# spectrum_1kHz_500Hz.net
KiCad netlist of a schematic drawn in Altium Designer
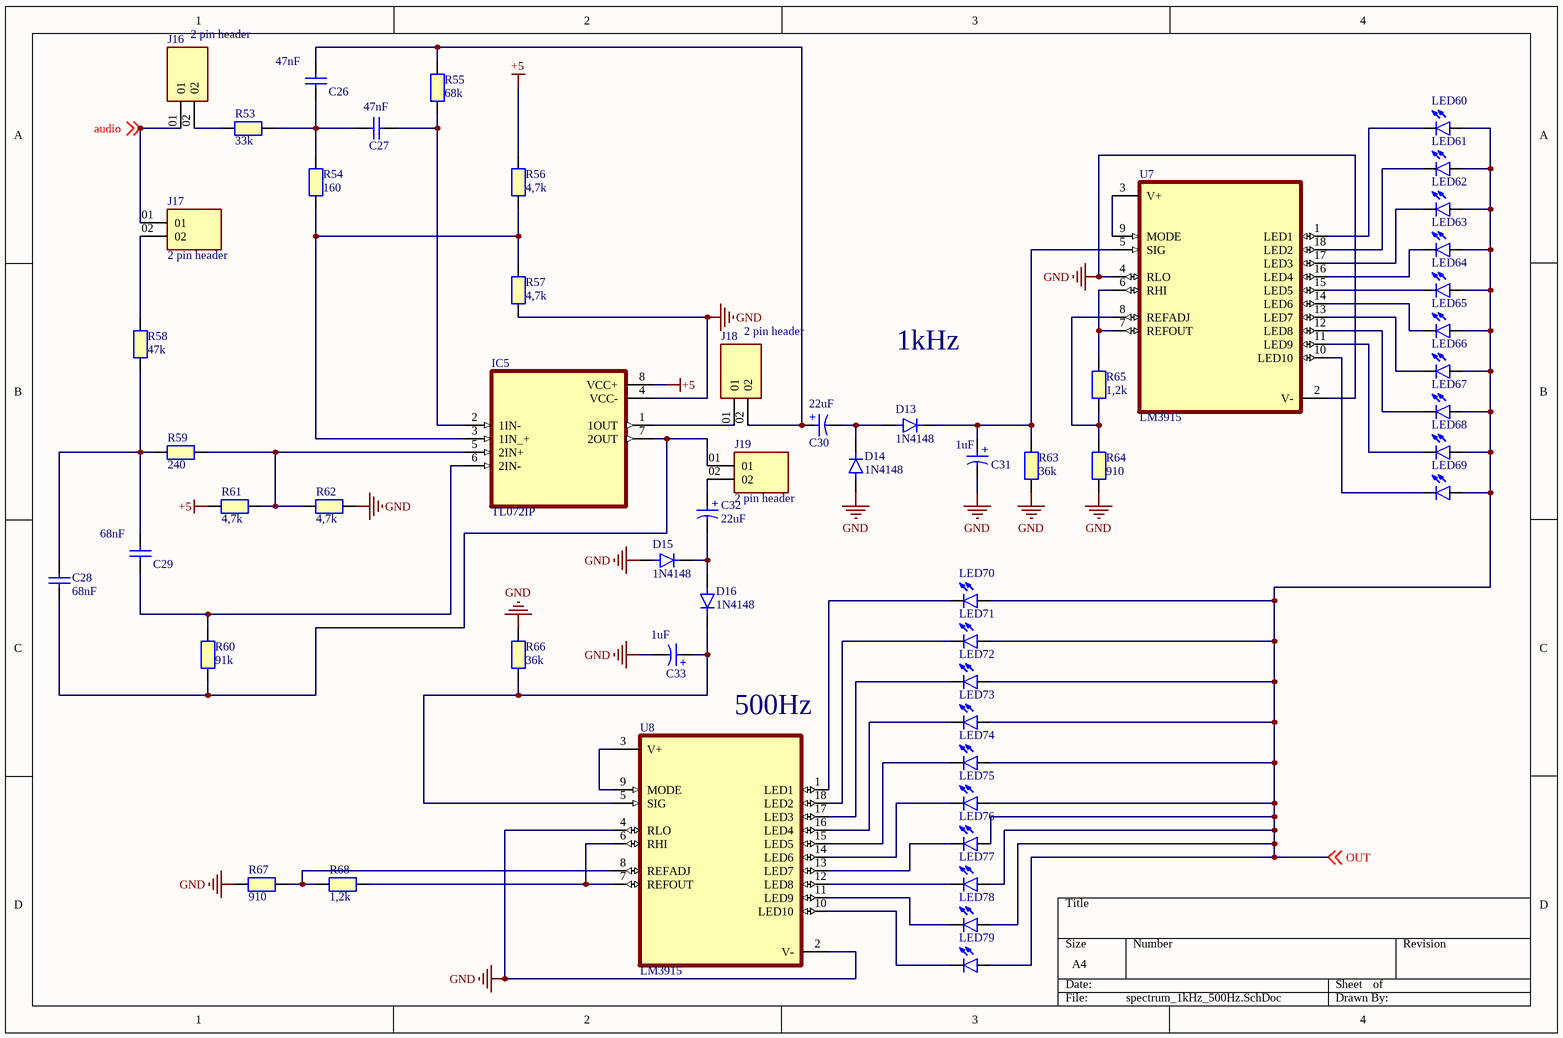
[diagram p0: spectrum_1kHz_500Hz.SchDoc]

(export (version "E")
  (design (tool "Eeschema 10.0.6"))
  (components
    (comp (ref "C26")
      (value "47nF")
      (footprint "CAPC2012X65N")
      (description "47nF ceramic")
      (fields
        (field (name "MANUFACTURER PART NUMBER") "885012004008")
        (field (name "MANUFACTURER") "Wurth Elektronik")
      )
      (libsource (lib "SpectrumComponents") (part "885012004008"))
    )
    (comp (ref "C27")
      (value "47nF")
      (footprint "CAPC2012X65N")
      (description "47nF ceramic")
      (fields
        (field (name "MANUFACTURER PART NUMBER") "885012004008")
        (field (name "MANUFACTURER") "Wurth Elektronik")
      )
      (libsource (lib "SpectrumComponents") (part "885012004008"))
    )
    (comp (ref "C28")
      (value "68nF")
      (footprint "CAPC2012X65N")
      (description "68nF ceramic")
      (fields
        (field (name "MANUFACTURER PART NUMBER") "885012004008")
        (field (name "MANUFACTURER") "Wurth Elektronik")
      )
      (libsource (lib "SpectrumComponents") (part "885012004008"))
    )
    (comp (ref "C29")
      (value "68nF")
      (footprint "CAPC2012X65N")
      (description "68nF ceramic")
      (fields
        (field (name "MANUFACTURER PART NUMBER") "885012004008")
        (field (name "MANUFACTURER") "Wurth Elektronik")
      )
      (libsource (lib "SpectrumComponents") (part "885012004008"))
    )
    (comp (ref "C30")
      (value "22uF")
      (footprint "WCAP-ATG8_D5H11")
      (description "Elco 22uF")
      (fields
        (field (name "MANUFACTURER PART NUMBER") "860010272005")
        (field (name "MANUFACTURER") "Wurth Elektronik")
      )
      (libsource (lib "SpectrumComponents") (part "860010272005"))
    )
    (comp (ref "C31")
      (value "1uF")
      (footprint "WCAP-ATG8_D5H11")
      (description "WCAP-ATG8 Aluminum Electrolytic Capacitor, Radial, THT, D5 x H11mm, 1uF, 10V")
      (fields
        (field (name "MANUFACTURER PART NUMBER") "860010272005")
        (field (name "MANUFACTURER") "Wurth Elektronik")
      )
      (libsource (lib "SpectrumComponents") (part "860010272005"))
    )
    (comp (ref "C32")
      (value "22uF")
      (footprint "WCAP-ATG8_D5H11")
      (description "Elco 22uF")
      (fields
        (field (name "MANUFACTURER PART NUMBER") "860010272005")
        (field (name "MANUFACTURER") "Wurth Elektronik")
      )
      (libsource (lib "SpectrumComponents") (part "860010272005"))
    )
    (comp (ref "C33")
      (value "1uF")
      (footprint "WCAP-ATG8_D5H11")
      (description "WCAP-ATG8 Aluminum Electrolytic Capacitor, Radial, THT, D5 x H11mm, 1µF, 10V")
      (fields
        (field (name "MANUFACTURER PART NUMBER") "860010272005")
        (field (name "MANUFACTURER") "Wurth Elektronik")
      )
      (libsource (lib "SpectrumComponents") (part "860010272005"))
    )
    (comp (ref "D13")
      (value "1N4148")
      (footprint "DIOAD829W49L456D191")
      (description "Diode Standard 75V 200mA Surface Mount SOD-523F")
      (fields (field (name "MF") "ON Semiconductor"))
      (libsource (lib "SpectrumComponents") (part "1N4148"))
    )
    (comp (ref "D14")
      (value "1N4148")
      (footprint "DIOAD829W49L456D191")
      (description "Diode Standard 75V 200mA Surface Mount SOD-523F")
      (fields (field (name "MF") "ON Semiconductor"))
      (libsource (lib "SpectrumComponents") (part "1N4148"))
    )
    (comp (ref "D15")
      (value "1N4148")
      (footprint "DIOAD829W49L456D191")
      (description "Diode Standard 75V 200mA Surface Mount SOD-523F")
      (fields (field (name "MF") "ON Semiconductor"))
      (libsource (lib "SpectrumComponents") (part "1N4148"))
    )
    (comp (ref "D16")
      (value "1N4148")
      (footprint "DIOAD829W49L456D191")
      (description "Diode Standard 75V 200mA Surface Mount SOD-523F")
      (fields (field (name "MF") "ON Semiconductor"))
      (libsource (lib "SpectrumComponents") (part "1N4148"))
    )
    (comp (ref "IC5")
      (value "TL072IP")
      (footprint "DIP794W45P254L959H508Q8")
      (description "Dual, 30-V, 3-MHz, high slew rate (13-V/Âµs), In to V+, JFET-input op amp")
      (fields (field (name "MF") "Texas Instruments"))
      (libsource (lib "SpectrumComponents") (part "TL072IP"))
    )
    (comp (ref "J16")
      (value "2 pin header")
      (footprint "SpectrumComponents:SAMTEC_HTSW-102-07-TM-S")
      (description "2 pin header Jumper")
      (fields (field (name "MP") "HTSW10207TMS") (field (name "MF") "Samtec"))
      (libsource (lib "SpectrumComponents") (part "2 pin header"))
    )
    (comp (ref "J17")
      (value "2 pin header")
      (footprint "SpectrumComponents:SAMTEC_HTSW-102-07-TM-S")
      (description "2 pin header Jumper")
      (fields (field (name "MP") "HTSW10207TMS") (field (name "MF") "Samtec"))
      (libsource (lib "") (part "2 pin header_1"))
    )
    (comp (ref "J18")
      (value "2 pin header")
      (footprint "SpectrumComponents:SAMTEC_HTSW-102-07-TM-S")
      (description "2 pin header Jumper")
      (fields (field (name "MP") "HTSW10207TMS") (field (name "MF") "Samtec"))
      (libsource (lib "SpectrumComponents") (part "2 pin header"))
    )
    (comp (ref "J19")
      (value "2 pin header")
      (footprint "SpectrumComponents:SAMTEC_HTSW-102-07-TM-S")
      (description "2 pin header Jumper")
      (fields (field (name "MP") "HTSW10207TMS") (field (name "MF") "Samtec"))
      (libsource (lib "") (part "2 pin header_1"))
    )
    (comp (ref "LED60")
      (value "LED 2x3x4")
      (footprint "LED 2x3x4mm")
      (description "Green 569nm LED Indication - Discrete 1.9V Radial")
      (fields (field (name "MP") "TLLG4400") (field (name "MF") "Vishay Semiconductors"))
      (libsource (lib "SpectrumComponents") (part "LED 2x3x4"))
    )
    (comp (ref "LED61")
      (value "LED 2x3x4")
      (footprint "LED 2x3x4mm")
      (description "Green 569nm LED Indication - Discrete 1.9V Radial")
      (fields (field (name "MP") "TLLG4400") (field (name "MF") "Vishay Semiconductors"))
      (libsource (lib "SpectrumComponents") (part "LED 2x3x4"))
    )
    (comp (ref "LED62")
      (value "LED 2x3x4")
      (footprint "LED 2x3x4mm")
      (description "Green 569nm LED Indication - Discrete 1.9V Radial")
      (fields (field (name "MP") "TLLG4400") (field (name "MF") "Vishay Semiconductors"))
      (libsource (lib "SpectrumComponents") (part "LED 2x3x4"))
    )
    (comp (ref "LED63")
      (value "LED 2x3x4")
      (footprint "LED 2x3x4mm")
      (description "Green 569nm LED Indication - Discrete 1.9V Radial")
      (fields (field (name "MP") "TLLG4400") (field (name "MF") "Vishay Semiconductors"))
      (libsource (lib "SpectrumComponents") (part "LED 2x3x4"))
    )
    (comp (ref "LED64")
      (value "LED 2x3x4")
      (footprint "LED 2x3x4mm")
      (description "Green 569nm LED Indication - Discrete 1.9V Radial")
      (fields (field (name "MP") "TLLG4400") (field (name "MF") "Vishay Semiconductors"))
      (libsource (lib "SpectrumComponents") (part "LED 2x3x4"))
    )
    (comp (ref "LED65")
      (value "LED 2x3x4")
      (footprint "LED 2x3x4mm")
      (description "Green 569nm LED Indication - Discrete 1.9V Radial")
      (fields (field (name "MP") "TLLG4400") (field (name "MF") "Vishay Semiconductors"))
      (libsource (lib "SpectrumComponents") (part "LED 2x3x4"))
    )
    (comp (ref "LED66")
      (value "LED 2x3x4")
      (footprint "LED 2x3x4mm")
      (description "Green 569nm LED Indication - Discrete 1.9V Radial")
      (fields (field (name "MP") "TLLG4400") (field (name "MF") "Vishay Semiconductors"))
      (libsource (lib "SpectrumComponents") (part "LED 2x3x4"))
    )
    (comp (ref "LED67")
      (value "LED 2x3x4")
      (footprint "LED 2x3x4mm")
      (description "Green 569nm LED Indication - Discrete 1.9V Radial")
      (fields (field (name "MP") "TLLG4400") (field (name "MF") "Vishay Semiconductors"))
      (libsource (lib "SpectrumComponents") (part "LED 2x3x4"))
    )
    (comp (ref "LED68")
      (value "LED 2x3x4")
      (footprint "LED 2x3x4mm")
      (description "Green 569nm LED Indication - Discrete 1.9V Radial")
      (fields (field (name "MP") "TLLG4400") (field (name "MF") "Vishay Semiconductors"))
      (libsource (lib "SpectrumComponents") (part "LED 2x3x4"))
    )
    (comp (ref "LED69")
      (value "LED 2x3x4")
      (footprint "LED 2x3x4mm")
      (description "Green 569nm LED Indication - Discrete 1.9V Radial")
      (fields (field (name "MP") "TLLG4400") (field (name "MF") "Vishay Semiconductors"))
      (libsource (lib "SpectrumComponents") (part "LED 2x3x4"))
    )
    (comp (ref "LED70")
      (value "LED 2x3x4")
      (footprint "LED 2x3x4mm")
      (description "Green 569nm LED Indication - Discrete 1.9V Radial")
      (fields (field (name "MP") "TLLG4400") (field (name "MF") "Vishay Semiconductors"))
      (libsource (lib "SpectrumComponents") (part "LED 2x3x4"))
    )
    (comp (ref "LED71")
      (value "LED 2x3x4")
      (footprint "LED 2x3x4mm")
      (description "Green 569nm LED Indication - Discrete 1.9V Radial")
      (fields (field (name "MP") "TLLG4400") (field (name "MF") "Vishay Semiconductors"))
      (libsource (lib "SpectrumComponents") (part "LED 2x3x4"))
    )
    (comp (ref "LED72")
      (value "LED 2x3x4")
      (footprint "LED 2x3x4mm")
      (description "Green 569nm LED Indication - Discrete 1.9V Radial")
      (fields (field (name "MP") "TLLG4400") (field (name "MF") "Vishay Semiconductors"))
      (libsource (lib "SpectrumComponents") (part "LED 2x3x4"))
    )
    (comp (ref "LED73")
      (value "LED 2x3x4")
      (footprint "LED 2x3x4mm")
      (description "Green 569nm LED Indication - Discrete 1.9V Radial")
      (fields (field (name "MP") "TLLG4400") (field (name "MF") "Vishay Semiconductors"))
      (libsource (lib "SpectrumComponents") (part "LED 2x3x4"))
    )
    (comp (ref "LED74")
      (value "LED 2x3x4")
      (footprint "LED 2x3x4mm")
      (description "Green 569nm LED Indication - Discrete 1.9V Radial")
      (fields (field (name "MP") "TLLG4400") (field (name "MF") "Vishay Semiconductors"))
      (libsource (lib "SpectrumComponents") (part "LED 2x3x4"))
    )
    (comp (ref "LED75")
      (value "LED 2x3x4")
      (footprint "LED 2x3x4mm")
      (description "Green 569nm LED Indication - Discrete 1.9V Radial")
      (fields (field (name "MP") "TLLG4400") (field (name "MF") "Vishay Semiconductors"))
      (libsource (lib "SpectrumComponents") (part "LED 2x3x4"))
    )
    (comp (ref "LED76")
      (value "LED 2x3x4")
      (footprint "LED 2x3x4mm")
      (description "Green 569nm LED Indication - Discrete 1.9V Radial")
      (fields (field (name "MP") "TLLG4400") (field (name "MF") "Vishay Semiconductors"))
      (libsource (lib "SpectrumComponents") (part "LED 2x3x4"))
    )
    (comp (ref "LED77")
      (value "LED 2x3x4")
      (footprint "LED 2x3x4mm")
      (description "Green 569nm LED Indication - Discrete 1.9V Radial")
      (fields (field (name "MP") "TLLG4400") (field (name "MF") "Vishay Semiconductors"))
      (libsource (lib "SpectrumComponents") (part "LED 2x3x4"))
    )
    (comp (ref "LED78")
      (value "LED 2x3x4")
      (footprint "LED 2x3x4mm")
      (description "Green 569nm LED Indication - Discrete 1.9V Radial")
      (fields (field (name "MP") "TLLG4400") (field (name "MF") "Vishay Semiconductors"))
      (libsource (lib "SpectrumComponents") (part "LED 2x3x4"))
    )
    (comp (ref "LED79")
      (value "LED 2x3x4")
      (footprint "LED 2x3x4mm")
      (description "Green 569nm LED Indication - Discrete 1.9V Radial")
      (fields (field (name "MP") "TLLG4400") (field (name "MF") "Vishay Semiconductors"))
      (libsource (lib "SpectrumComponents") (part "LED 2x3x4"))
    )
    (comp (ref "R53")
      (value "33k")
      (footprint "RESC2012X50N")
      (description "33k Resistor 0805")
      (fields (field (name "PART NUMBER") "TNPW080510K0BETA") (field (name "MANUFACTURER") "Vishay Dale"))
      (libsource (lib "") (part "RESISTOR 0805_3"))
    )
    (comp (ref "R54")
      (value "160")
      (footprint "RESC2012X50N")
      (description "160Ohm Resistor 0805")
      (fields (field (name "PART NUMBER") "TNPW080510K0BETA") (field (name "MANUFACTURER") "Vishay Dale"))
      (libsource (lib "SpectrumComponents") (part "RESISTOR 0805"))
    )
    (comp (ref "R55")
      (value "68k")
      (footprint "RESC2012X50N")
      (description "68k Resistor 0805")
      (fields (field (name "PART NUMBER") "TNPW080510K0BETA") (field (name "MANUFACTURER") "Vishay Dale"))
      (libsource (lib "SpectrumComponents") (part "RESISTOR 0805"))
    )
    (comp (ref "R56")
      (value "4,7k")
      (footprint "RESC2012X50N")
      (description "4,7k Resistor 0805")
      (fields (field (name "PART NUMBER") "TNPW080510K0BETA") (field (name "MANUFACTURER") "Vishay Dale"))
      (libsource (lib "SpectrumComponents") (part "RESISTOR 0805"))
    )
    (comp (ref "R57")
      (value "4,7k")
      (footprint "RESC2012X50N")
      (description "4,7k Resistor 0805")
      (fields (field (name "PART NUMBER") "TNPW080510K0BETA") (field (name "MANUFACTURER") "Vishay Dale"))
      (libsource (lib "SpectrumComponents") (part "RESISTOR 0805"))
    )
    (comp (ref "R58")
      (value "47k")
      (footprint "RESC2012X50N")
      (description "47k Resistor 0805")
      (fields (field (name "PART NUMBER") "TNPW080510K0BETA") (field (name "MANUFACTURER") "Vishay Dale"))
      (libsource (lib "SpectrumComponents") (part "RESISTOR 0805"))
    )
    (comp (ref "R59")
      (value "240")
      (footprint "RESC2012X50N")
      (description "240 resistor 0805")
      (fields (field (name "PART NUMBER") "TNPW080510K0BETA") (field (name "MANUFACTURER") "Vishay Dale"))
      (libsource (lib "") (part "RESISTOR 0805_1"))
    )
    (comp (ref "R60")
      (value "91k")
      (footprint "RESC2012X50N")
      (description "91k Resistor 0805")
      (fields (field (name "PART NUMBER") "TNPW080510K0BETA") (field (name "MANUFACTURER") "Vishay Dale"))
      (libsource (lib "SpectrumComponents") (part "RESISTOR 0805"))
    )
    (comp (ref "R61")
      (value "4,7k")
      (footprint "RESC2012X50N")
      (description "4,7k Resistor 0805")
      (fields (field (name "PART NUMBER") "TNPW080510K0BETA") (field (name "MANUFACTURER") "Vishay Dale"))
      (libsource (lib "") (part "RESISTOR 0805_1"))
    )
    (comp (ref "R62")
      (value "4,7k")
      (footprint "RESC2012X50N")
      (description "4,7k Resistor 0805")
      (fields (field (name "PART NUMBER") "TNPW080510K0BETA") (field (name "MANUFACTURER") "Vishay Dale"))
      (libsource (lib "") (part "RESISTOR 0805_3"))
    )
    (comp (ref "R63")
      (value "36k")
      (footprint "RESC2012X50N")
      (description "36k Resistor 0805")
      (fields (field (name "PART NUMBER") "TNPW080510K0BETA") (field (name "MANUFACTURER") "Vishay Dale"))
      (libsource (lib "SpectrumComponents") (part "RESISTOR 0805"))
    )
    (comp (ref "R64")
      (value "910")
      (footprint "RESC2012X50N")
      (description "910 Resistor 0805")
      (fields (field (name "PART NUMBER") "TNPW080510K0BETA") (field (name "MANUFACTURER") "Vishay Dale"))
      (libsource (lib "") (part "RESISTOR 0805_2"))
    )
    (comp (ref "R65")
      (value "1,2k")
      (footprint "RESC2012X50N")
      (description "1,2k Resistor 0805")
      (fields (field (name "PART NUMBER") "TNPW080510K0BETA") (field (name "MANUFACTURER") "Vishay Dale"))
      (libsource (lib "") (part "RESISTOR 0805_2"))
    )
    (comp (ref "R66")
      (value "36k")
      (footprint "RESC2012X50N")
      (description "4,7k Resistor 0805")
      (fields (field (name "PART NUMBER") "TNPW080510K0BETA") (field (name "MANUFACTURER") "Vishay Dale"))
      (libsource (lib "") (part "RESISTOR 0805_2"))
    )
    (comp (ref "R67")
      (value "910")
      (footprint "RESC2012X50N")
      (description "910 Resistor 0805")
      (fields (field (name "PART NUMBER") "TNPW080510K0BETA") (field (name "MANUFACTURER") "Vishay Dale"))
      (libsource (lib "") (part "RESISTOR 0805_1"))
    )
    (comp (ref "R68")
      (value "1,2k")
      (footprint "RESC2012X50N")
      (description "1,2k Resistor 0805")
      (fields (field (name "PART NUMBER") "TNPW080510K0BETA") (field (name "MANUFACTURER") "Vishay Dale"))
      (libsource (lib "") (part "RESISTOR 0805_1"))
    )
    (comp (ref "U7")
      (value "LM3915")
      (footprint "SpectrumComponents:DIP952W45P254L2336H533Q18")
      (fields (field (name "MP") "LM3914N-1"))
      (libsource (lib "SpectrumComponents") (part "LM3915"))
    )
    (comp (ref "U8")
      (value "LM3915")
      (footprint "SpectrumComponents:DIP952W45P254L2336H533Q18")
      (fields (field (name "MP") "LM3914N-1"))
      (libsource (lib "SpectrumComponents") (part "LM3915"))
    )
  )
  (nets
    (net (code "1") (name "+5") (class "Default")
      (node (ref "IC5") (pin "8") (pinfunction "VCC+_8") (pintype "power_in"))
      (node (ref "R56") (pin "2") (pinfunction "2_2") (pintype "passive"))
      (node (ref "R61") (pin "2") (pinfunction "2_2") (pintype "passive"))
    )
    (net (code "2") (name "GND") (class "Default")
      (node (ref "C31") (pin "2") (pinfunction "N_2") (pintype "passive"))
      (node (ref "C33") (pin "2") (pinfunction "N_2") (pintype "passive"))
      (node (ref "D14") (pin "A") (pinfunction "A_A") (pintype "passive"))
      (node (ref "D15") (pin "A") (pinfunction "A_A") (pintype "passive"))
      (node (ref "IC5") (pin "4") (pinfunction "VCC-_4") (pintype "power_in"))
      (node (ref "R57") (pin "1") (pinfunction "1_1") (pintype "passive"))
      (node (ref "R62") (pin "2") (pinfunction "2_2") (pintype "passive"))
      (node (ref "R63") (pin "1") (pinfunction "1_1") (pintype "passive"))
      (node (ref "R64") (pin "2") (pinfunction "2_2") (pintype "passive"))
      (node (ref "R66") (pin "1") (pinfunction "1_1") (pintype "passive"))
      (node (ref "R67") (pin "2") (pinfunction "2_2") (pintype "passive"))
      (node (ref "U7") (pin "2") (pinfunction "V-_2") (pintype "power_in"))
      (node (ref "U7") (pin "4") (pinfunction "RLO_4") (pintype "bidirectional"))
      (node (ref "U8") (pin "2") (pinfunction "V-_2") (pintype "power_in"))
      (node (ref "U8") (pin "4") (pinfunction "RLO_4") (pintype "bidirectional"))
    )
    (net (code "3") (name "Net-(C26-Pad1)") (class "Default")
      (node (ref "C26") (pin "1") (pinfunction "1_1") (pintype "passive"))
      (node (ref "C27") (pin "1") (pinfunction "1_1") (pintype "passive"))
      (node (ref "R53") (pin "2") (pinfunction "2_2") (pintype "passive"))
      (node (ref "R54") (pin "2") (pinfunction "2_2") (pintype "passive"))
    )
    (net (code "4") (name "Net-(C28-Pad2)") (class "Default")
      (node (ref "C28") (pin "2") (pinfunction "2_2") (pintype "passive"))
      (node (ref "C29") (pin "2") (pinfunction "2_2") (pintype "passive"))
      (node (ref "R58") (pin "1") (pinfunction "1_1") (pintype "passive"))
      (node (ref "R59") (pin "2") (pinfunction "2_2") (pintype "passive"))
    )
    (net (code "5") (name "Net-(C30-N)") (class "Default")
      (node (ref "C30") (pin "2") (pinfunction "N_2") (pintype "passive"))
      (node (ref "D13") (pin "A") (pinfunction "A_A") (pintype "passive"))
      (node (ref "D14") (pin "C") (pinfunction "C_C") (pintype "passive"))
    )
    (net (code "6") (name "Net-(C30-P)") (class "Default")
      (node (ref "C26") (pin "2") (pinfunction "2_2") (pintype "passive"))
      (node (ref "C30") (pin "1") (pinfunction "P_1") (pintype "passive"))
      (node (ref "J18") (pin "02") (pinfunction "02_02") (pintype "passive"))
      (node (ref "R55") (pin "2") (pinfunction "2_2") (pintype "passive"))
    )
    (net (code "7") (name "Net-(C31-P)") (class "Default")
      (node (ref "C31") (pin "1") (pinfunction "P_1") (pintype "passive"))
      (node (ref "D13") (pin "C") (pinfunction "C_C") (pintype "passive"))
      (node (ref "R63") (pin "2") (pinfunction "2_2") (pintype "passive"))
      (node (ref "U7") (pin "5") (pinfunction "SIG_5") (pintype "input"))
    )
    (net (code "8") (name "Net-(C32-N)") (class "Default")
      (node (ref "C32") (pin "2") (pinfunction "N_2") (pintype "passive"))
      (node (ref "D15") (pin "C") (pinfunction "C_C") (pintype "passive"))
      (node (ref "D16") (pin "A") (pinfunction "A_A") (pintype "passive"))
    )
    (net (code "9") (name "Net-(C32-P)") (class "Default")
      (node (ref "C32") (pin "1") (pinfunction "P_1") (pintype "passive"))
      (node (ref "J19") (pin "02") (pinfunction "02_02") (pintype "passive"))
    )
    (net (code "10") (name "Net-(C33-P)") (class "Default")
      (node (ref "C33") (pin "1") (pinfunction "P_1") (pintype "passive"))
      (node (ref "D16") (pin "C") (pinfunction "C_C") (pintype "passive"))
      (node (ref "R66") (pin "2") (pinfunction "2_2") (pintype "passive"))
      (node (ref "U8") (pin "5") (pinfunction "SIG_5") (pintype "input"))
    )
    (net (code "11") (name "Net-(IC5-1IN-)") (class "Default")
      (node (ref "C27") (pin "2") (pinfunction "2_2") (pintype "passive"))
      (node (ref "IC5") (pin "2") (pinfunction "1IN-_2") (pintype "input"))
      (node (ref "R55") (pin "1") (pinfunction "1_1") (pintype "passive"))
    )
    (net (code "12") (name "Net-(IC5-1IN_+)") (class "Default")
      (node (ref "IC5") (pin "3") (pinfunction "1IN_+_3") (pintype "input"))
      (node (ref "R54") (pin "1") (pinfunction "1_1") (pintype "passive"))
      (node (ref "R56") (pin "1") (pinfunction "1_1") (pintype "passive"))
      (node (ref "R57") (pin "2") (pinfunction "2_2") (pintype "passive"))
    )
    (net (code "13") (name "Net-(IC5-1OUT)") (class "Default")
      (node (ref "IC5") (pin "1") (pinfunction "1OUT_1") (pintype "output"))
      (node (ref "J18") (pin "01") (pinfunction "01_01") (pintype "passive"))
    )
    (net (code "14") (name "Net-(IC5-2IN+)") (class "Default")
      (node (ref "IC5") (pin "5") (pinfunction "2IN+_5") (pintype "input"))
      (node (ref "R59") (pin "1") (pinfunction "1_1") (pintype "passive"))
      (node (ref "R61") (pin "1") (pinfunction "1_1") (pintype "passive"))
      (node (ref "R62") (pin "1") (pinfunction "1_1") (pintype "passive"))
    )
    (net (code "15") (name "Net-(IC5-2IN-)") (class "Default")
      (node (ref "C29") (pin "1") (pinfunction "1_1") (pintype "passive"))
      (node (ref "IC5") (pin "6") (pinfunction "2IN-_6") (pintype "input"))
      (node (ref "R60") (pin "2") (pinfunction "2_2") (pintype "passive"))
    )
    (net (code "16") (name "Net-(IC5-2OUT)") (class "Default")
      (node (ref "C28") (pin "1") (pinfunction "1_1") (pintype "passive"))
      (node (ref "IC5") (pin "7") (pinfunction "2OUT_7") (pintype "output"))
      (node (ref "J19") (pin "01") (pinfunction "01_01") (pintype "passive"))
      (node (ref "R60") (pin "1") (pinfunction "1_1") (pintype "passive"))
    )
    (net (code "17") (name "Net-(J16-Pad02)") (class "Default")
      (node (ref "J16") (pin "02") (pinfunction "02_02") (pintype "passive"))
      (node (ref "R53") (pin "1") (pinfunction "1_1") (pintype "passive"))
    )
    (net (code "18") (name "Net-(J17-Pad02)") (class "Default")
      (node (ref "J17") (pin "02") (pinfunction "02_02") (pintype "passive"))
      (node (ref "R58") (pin "2") (pinfunction "2_2") (pintype "passive"))
    )
    (net (code "19") (name "Net-(LED60-C)") (class "Default")
      (node (ref "LED60") (pin "K") (pinfunction "C_K") (pintype "passive"))
      (node (ref "U7") (pin "1") (pinfunction "LED1_1") (pintype "bidirectional"))
    )
    (net (code "20") (name "Net-(LED61-C)") (class "Default")
      (node (ref "LED61") (pin "K") (pinfunction "C_K") (pintype "passive"))
      (node (ref "U7") (pin "18") (pinfunction "LED2_18") (pintype "bidirectional"))
    )
    (net (code "21") (name "Net-(LED62-C)") (class "Default")
      (node (ref "LED62") (pin "K") (pinfunction "C_K") (pintype "passive"))
      (node (ref "U7") (pin "17") (pinfunction "LED3_17") (pintype "bidirectional"))
    )
    (net (code "22") (name "Net-(LED63-C)") (class "Default")
      (node (ref "LED63") (pin "K") (pinfunction "C_K") (pintype "passive"))
      (node (ref "U7") (pin "16") (pinfunction "LED4_16") (pintype "bidirectional"))
    )
    (net (code "23") (name "Net-(LED64-C)") (class "Default")
      (node (ref "LED64") (pin "K") (pinfunction "C_K") (pintype "passive"))
      (node (ref "U7") (pin "15") (pinfunction "LED5_15") (pintype "bidirectional"))
    )
    (net (code "24") (name "Net-(LED65-C)") (class "Default")
      (node (ref "LED65") (pin "K") (pinfunction "C_K") (pintype "passive"))
      (node (ref "U7") (pin "14") (pinfunction "LED6_14") (pintype "bidirectional"))
    )
    (net (code "25") (name "Net-(LED66-C)") (class "Default")
      (node (ref "LED66") (pin "K") (pinfunction "C_K") (pintype "passive"))
      (node (ref "U7") (pin "13") (pinfunction "LED7_13") (pintype "bidirectional"))
    )
    (net (code "26") (name "Net-(LED67-C)") (class "Default")
      (node (ref "LED67") (pin "K") (pinfunction "C_K") (pintype "passive"))
      (node (ref "U7") (pin "12") (pinfunction "LED8_12") (pintype "bidirectional"))
    )
    (net (code "27") (name "Net-(LED68-C)") (class "Default")
      (node (ref "LED68") (pin "K") (pinfunction "C_K") (pintype "passive"))
      (node (ref "U7") (pin "11") (pinfunction "LED9_11") (pintype "bidirectional"))
    )
    (net (code "28") (name "Net-(LED69-C)") (class "Default")
      (node (ref "LED69") (pin "K") (pinfunction "C_K") (pintype "passive"))
      (node (ref "U7") (pin "10") (pinfunction "LED10_10") (pintype "bidirectional"))
    )
    (net (code "29") (name "Net-(LED70-C)") (class "Default")
      (node (ref "LED70") (pin "K") (pinfunction "C_K") (pintype "passive"))
      (node (ref "U8") (pin "1") (pinfunction "LED1_1") (pintype "bidirectional"))
    )
    (net (code "30") (name "Net-(LED71-C)") (class "Default")
      (node (ref "LED71") (pin "K") (pinfunction "C_K") (pintype "passive"))
      (node (ref "U8") (pin "18") (pinfunction "LED2_18") (pintype "bidirectional"))
    )
    (net (code "31") (name "Net-(LED72-C)") (class "Default")
      (node (ref "LED72") (pin "K") (pinfunction "C_K") (pintype "passive"))
      (node (ref "U8") (pin "17") (pinfunction "LED3_17") (pintype "bidirectional"))
    )
    (net (code "32") (name "Net-(LED73-C)") (class "Default")
      (node (ref "LED73") (pin "K") (pinfunction "C_K") (pintype "passive"))
      (node (ref "U8") (pin "16") (pinfunction "LED4_16") (pintype "bidirectional"))
    )
    (net (code "33") (name "Net-(LED74-C)") (class "Default")
      (node (ref "LED74") (pin "K") (pinfunction "C_K") (pintype "passive"))
      (node (ref "U8") (pin "15") (pinfunction "LED5_15") (pintype "bidirectional"))
    )
    (net (code "34") (name "Net-(LED75-C)") (class "Default")
      (node (ref "LED75") (pin "K") (pinfunction "C_K") (pintype "passive"))
      (node (ref "U8") (pin "14") (pinfunction "LED6_14") (pintype "bidirectional"))
    )
    (net (code "35") (name "Net-(LED76-C)") (class "Default")
      (node (ref "LED76") (pin "K") (pinfunction "C_K") (pintype "passive"))
      (node (ref "U8") (pin "13") (pinfunction "LED7_13") (pintype "bidirectional"))
    )
    (net (code "36") (name "Net-(LED77-C)") (class "Default")
      (node (ref "LED77") (pin "K") (pinfunction "C_K") (pintype "passive"))
      (node (ref "U8") (pin "12") (pinfunction "LED8_12") (pintype "bidirectional"))
    )
    (net (code "37") (name "Net-(LED78-C)") (class "Default")
      (node (ref "LED78") (pin "K") (pinfunction "C_K") (pintype "passive"))
      (node (ref "U8") (pin "11") (pinfunction "LED9_11") (pintype "bidirectional"))
    )
    (net (code "38") (name "Net-(LED79-C)") (class "Default")
      (node (ref "LED79") (pin "K") (pinfunction "C_K") (pintype "passive"))
      (node (ref "U8") (pin "10") (pinfunction "LED10_10") (pintype "bidirectional"))
    )
    (net (code "39") (name "Net-(U7-MODE)") (class "Default")
      (node (ref "U7") (pin "3") (pinfunction "V+_3") (pintype "power_in"))
      (node (ref "U7") (pin "9") (pinfunction "MODE_9") (pintype "input"))
    )
    (net (code "40") (name "Net-(U7-REFADJ)") (class "Default")
      (node (ref "R64") (pin "1") (pinfunction "1_1") (pintype "passive"))
      (node (ref "R65") (pin "2") (pinfunction "2_2") (pintype "passive"))
      (node (ref "U7") (pin "8") (pinfunction "REFADJ_8") (pintype "bidirectional"))
    )
    (net (code "41") (name "Net-(U7-REFOUT)") (class "Default")
      (node (ref "R65") (pin "1") (pinfunction "1_1") (pintype "passive"))
      (node (ref "U7") (pin "6") (pinfunction "RHI_6") (pintype "bidirectional"))
      (node (ref "U7") (pin "7") (pinfunction "REFOUT_7") (pintype "bidirectional"))
    )
    (net (code "42") (name "Net-(U8-MODE)") (class "Default")
      (node (ref "U8") (pin "3") (pinfunction "V+_3") (pintype "power_in"))
      (node (ref "U8") (pin "9") (pinfunction "MODE_9") (pintype "input"))
    )
    (net (code "43") (name "Net-(U8-REFADJ)") (class "Default")
      (node (ref "R67") (pin "1") (pinfunction "1_1") (pintype "passive"))
      (node (ref "R68") (pin "2") (pinfunction "2_2") (pintype "passive"))
      (node (ref "U8") (pin "8") (pinfunction "REFADJ_8") (pintype "bidirectional"))
    )
    (net (code "44") (name "Net-(U8-REFOUT)") (class "Default")
      (node (ref "R68") (pin "1") (pinfunction "1_1") (pintype "passive"))
      (node (ref "U8") (pin "6") (pinfunction "RHI_6") (pintype "bidirectional"))
      (node (ref "U8") (pin "7") (pinfunction "REFOUT_7") (pintype "bidirectional"))
    )
    (net (code "45") (name "OUT") (class "Default")
      (node (ref "LED60") (pin "A") (pinfunction "A_A") (pintype "passive"))
      (node (ref "LED61") (pin "A") (pinfunction "A_A") (pintype "passive"))
      (node (ref "LED62") (pin "A") (pinfunction "A_A") (pintype "passive"))
      (node (ref "LED63") (pin "A") (pinfunction "A_A") (pintype "passive"))
      (node (ref "LED64") (pin "A") (pinfunction "A_A") (pintype "passive"))
      (node (ref "LED65") (pin "A") (pinfunction "A_A") (pintype "passive"))
      (node (ref "LED66") (pin "A") (pinfunction "A_A") (pintype "passive"))
      (node (ref "LED67") (pin "A") (pinfunction "A_A") (pintype "passive"))
      (node (ref "LED68") (pin "A") (pinfunction "A_A") (pintype "passive"))
      (node (ref "LED69") (pin "A") (pinfunction "A_A") (pintype "passive"))
      (node (ref "LED70") (pin "A") (pinfunction "A_A") (pintype "passive"))
      (node (ref "LED71") (pin "A") (pinfunction "A_A") (pintype "passive"))
      (node (ref "LED72") (pin "A") (pinfunction "A_A") (pintype "passive"))
      (node (ref "LED73") (pin "A") (pinfunction "A_A") (pintype "passive"))
      (node (ref "LED74") (pin "A") (pinfunction "A_A") (pintype "passive"))
      (node (ref "LED75") (pin "A") (pinfunction "A_A") (pintype "passive"))
      (node (ref "LED76") (pin "A") (pinfunction "A_A") (pintype "passive"))
      (node (ref "LED77") (pin "A") (pinfunction "A_A") (pintype "passive"))
      (node (ref "LED78") (pin "A") (pinfunction "A_A") (pintype "passive"))
      (node (ref "LED79") (pin "A") (pinfunction "A_A") (pintype "passive"))
    )
    (net (code "46") (name "audio") (class "Default")
      (node (ref "J16") (pin "01") (pinfunction "01_01") (pintype "passive"))
      (node (ref "J17") (pin "01") (pinfunction "01_01") (pintype "passive"))
    )
  )
)
